# Main_Schematics.net
KiCad netlist of a schematic drawn in Altium Designer
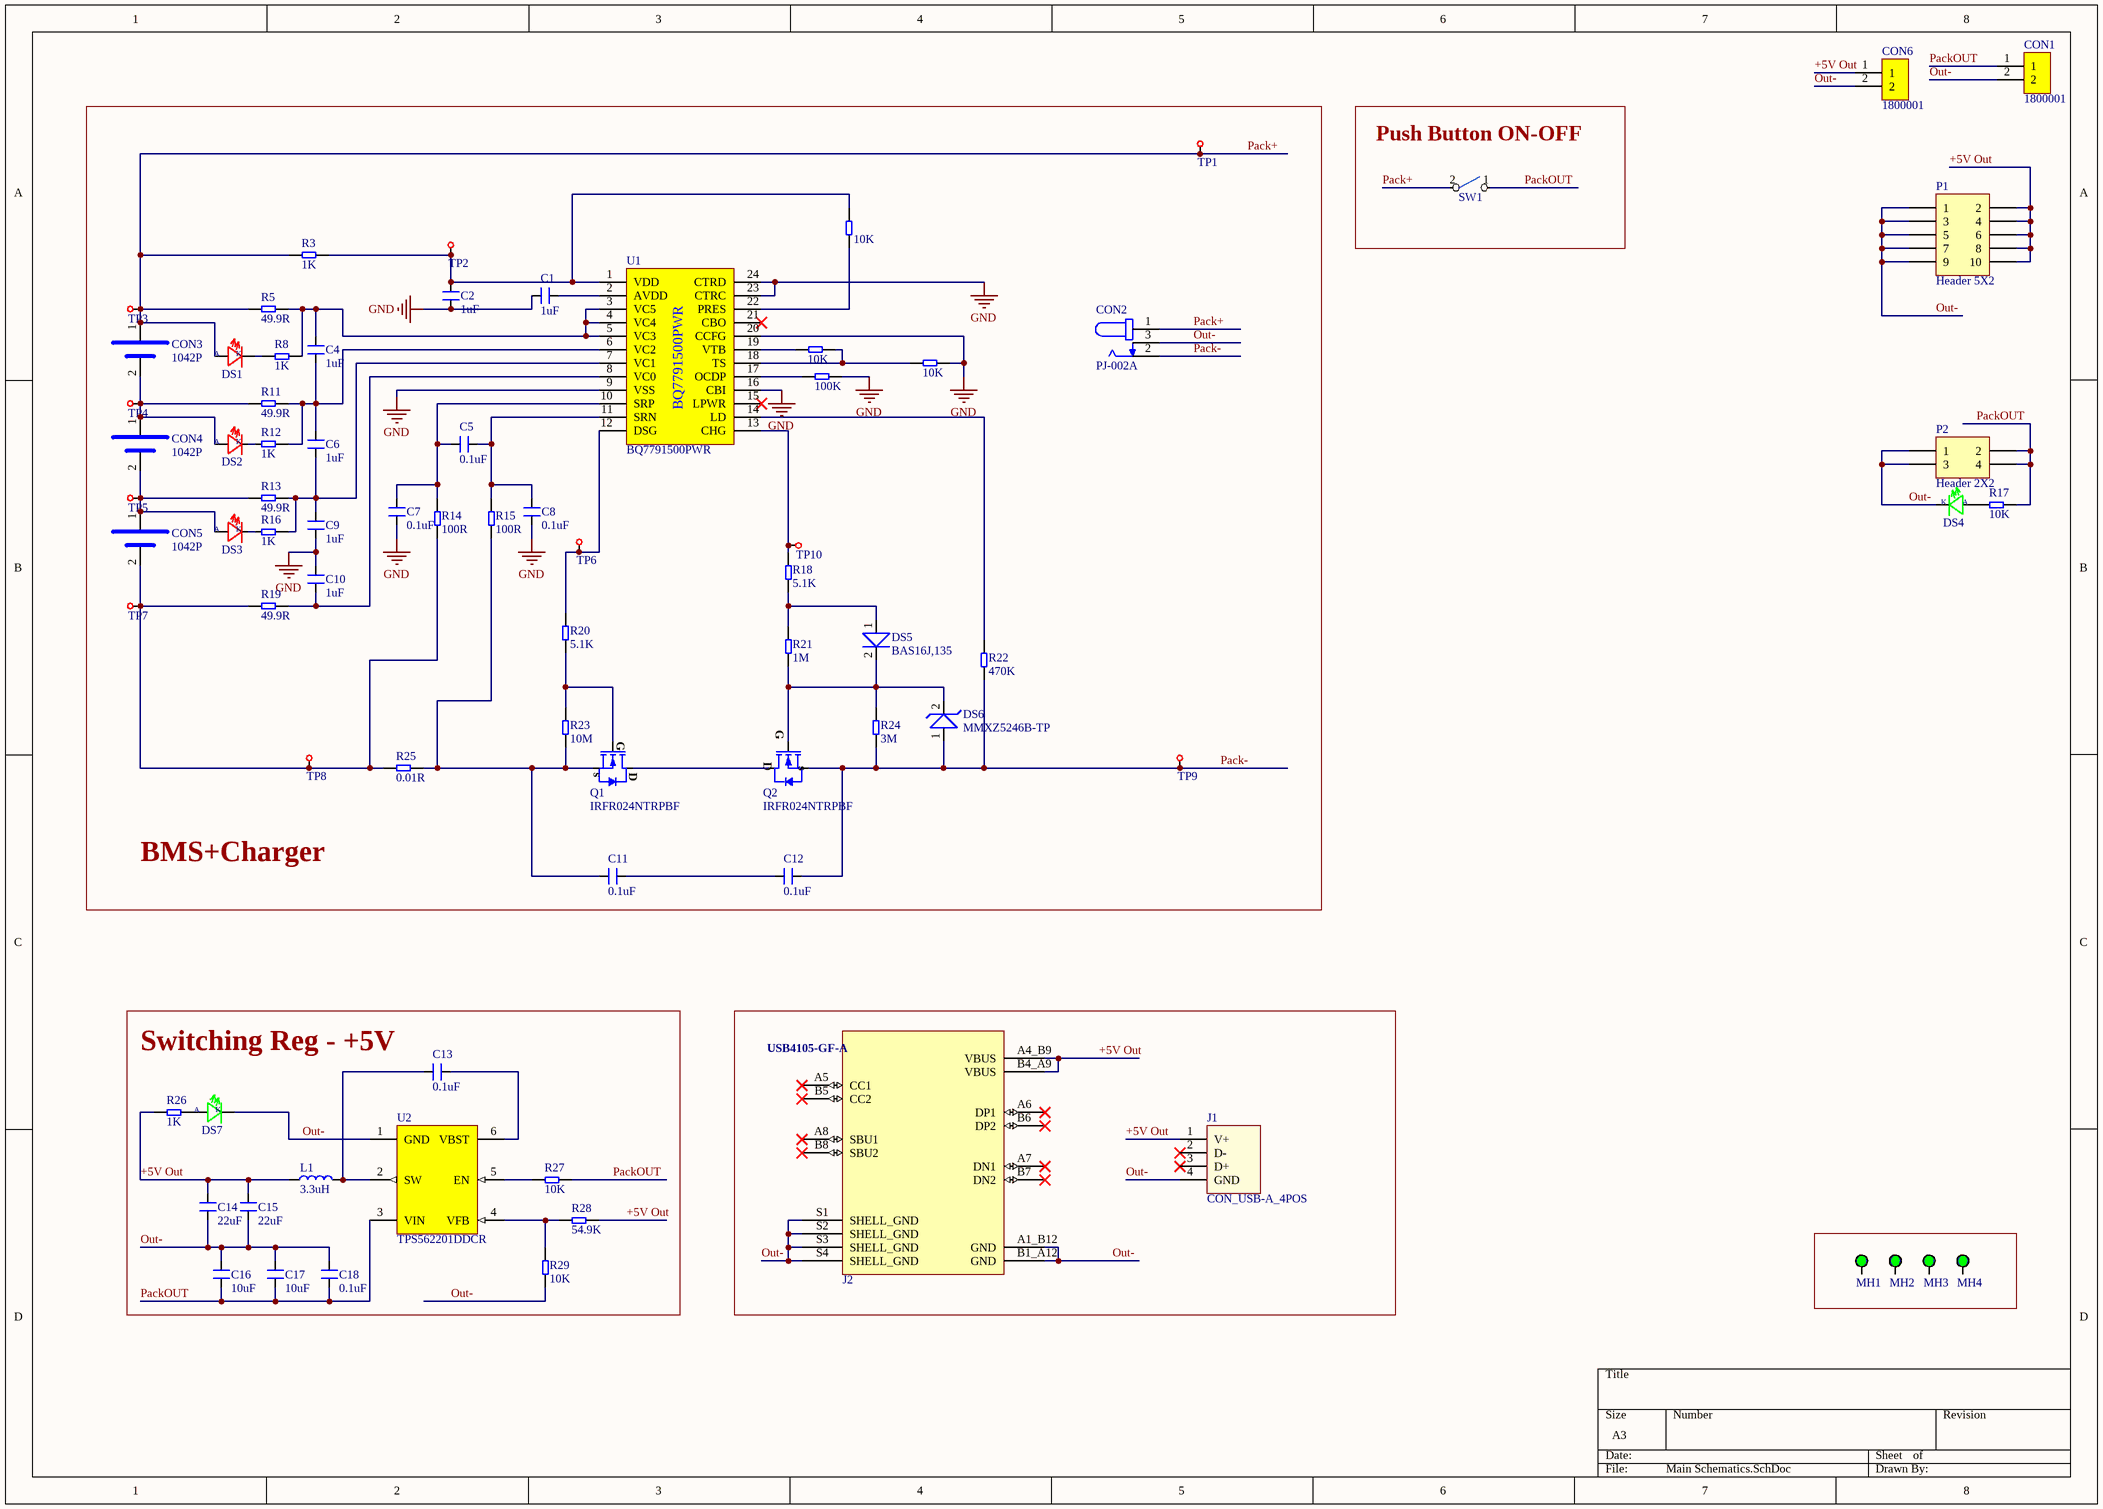
[diagram p0: Main Schematics.SchDoc]

(export (version "E")
  (design (tool "Eeschema 10.0.6"))
  (components
    (comp (ref "C1")
      (value "1uF")
      (footprint "CAP_0805")
      (description "Cap, 1UF, 16V, Mlcc, 0805;")
      (fields
        (field (name "MANUFACTURER") "KEMET")
        (field (name "MANUFACTURER PART NUMBER") "C0805C105Z4VAC7210")
      )
      (libsource (lib "HK_ALTIUM_COM_LIB") (part "CAP_1uF_16V_20%_0805"))
    )
    (comp (ref "C2")
      (value "1uF")
      (footprint "CAP_0805")
      (description "Cap, 1UF, 16V, Mlcc, 0805;")
      (fields
        (field (name "MANUFACTURER") "KEMET")
        (field (name "MANUFACTURER PART NUMBER") "C0805C105Z4VAC7210")
      )
      (libsource (lib "HK_ALTIUM_COM_LIB") (part "CAP_1uF_16V_20%_0805"))
    )
    (comp (ref "C4")
      (value "1uF")
      (footprint "CAP_0805")
      (description "Cap, 1UF, 16V, Mlcc, 0805;")
      (fields
        (field (name "MANUFACTURER") "KEMET")
        (field (name "MANUFACTURER PART NUMBER") "C0805C105Z4VAC7210")
      )
      (libsource (lib "HK_ALTIUM_COM_LIB") (part "CAP_1uF_16V_20%_0805"))
    )
    (comp (ref "C5")
      (value "0.1uF")
      (footprint "CAP_0805")
      (description "Multilayer Ceramic Capacitor, 0.1 uF, 16 V, ± 10%, X7R, 0805 [2012 Metric]")
      (fields
        (field (name "MANUFACTURER") "KEMET")
        (field (name "MANUFACTURER PART NUMBER") "C0805C104K4RACTU")
      )
      (libsource (lib "HK_ALTIUM_COM_LIB") (part "CAP_0.1uF_16V_10%_0805"))
    )
    (comp (ref "C6")
      (value "1uF")
      (footprint "CAP_0805")
      (description "Cap, 1UF, 16V, Mlcc, 0805;")
      (fields
        (field (name "MANUFACTURER") "KEMET")
        (field (name "MANUFACTURER PART NUMBER") "C0805C105Z4VAC7210")
      )
      (libsource (lib "HK_ALTIUM_COM_LIB") (part "CAP_1uF_16V_20%_0805"))
    )
    (comp (ref "C7")
      (value "0.1uF")
      (footprint "CAP_0805")
      (description "Multilayer Ceramic Capacitor, 0.1 uF, 16 V, ± 10%, X7R, 0805 [2012 Metric]")
      (fields
        (field (name "MANUFACTURER") "KEMET")
        (field (name "MANUFACTURER PART NUMBER") "C0805C104K4RACTU")
      )
      (libsource (lib "HK_ALTIUM_COM_LIB") (part "CAP_0.1uF_16V_10%_0805"))
    )
    (comp (ref "C8")
      (value "0.1uF")
      (footprint "CAP_0805")
      (description "Multilayer Ceramic Capacitor, 0.1 uF, 16 V, ± 10%, X7R, 0805 [2012 Metric]")
      (fields
        (field (name "MANUFACTURER") "KEMET")
        (field (name "MANUFACTURER PART NUMBER") "C0805C104K4RACTU")
      )
      (libsource (lib "HK_ALTIUM_COM_LIB") (part "CAP_0.1uF_16V_10%_0805"))
    )
    (comp (ref "C9")
      (value "1uF")
      (footprint "CAP_0805")
      (description "Cap, 1UF, 16V, Mlcc, 0805;")
      (fields
        (field (name "MANUFACTURER") "KEMET")
        (field (name "MANUFACTURER PART NUMBER") "C0805C105Z4VAC7210")
      )
      (libsource (lib "HK_ALTIUM_COM_LIB") (part "CAP_1uF_16V_20%_0805"))
    )
    (comp (ref "C10")
      (value "1uF")
      (footprint "CAP_0805")
      (description "Cap, 1UF, 16V, Mlcc, 0805;")
      (fields
        (field (name "MANUFACTURER") "KEMET")
        (field (name "MANUFACTURER PART NUMBER") "C0805C105Z4VAC7210")
      )
      (libsource (lib "HK_ALTIUM_COM_LIB") (part "CAP_1uF_16V_20%_0805"))
    )
    (comp (ref "C11")
      (value "0.1uF")
      (footprint "CAP_0805")
      (description "Multilayer Ceramic Capacitor, 0.1 uF, 16 V, ± 10%, X7R, 0805 [2012 Metric]")
      (fields
        (field (name "MANUFACTURER") "KEMET")
        (field (name "MANUFACTURER PART NUMBER") "C0805C104K4RACTU")
      )
      (libsource (lib "HK_ALTIUM_COM_LIB") (part "CAP_0.1uF_16V_10%_0805"))
    )
    (comp (ref "C12")
      (value "0.1uF")
      (footprint "CAP_0805")
      (description "Multilayer Ceramic Capacitor, 0.1 uF, 16 V, ± 10%, X7R, 0805 [2012 Metric]")
      (fields
        (field (name "MANUFACTURER") "KEMET")
        (field (name "MANUFACTURER PART NUMBER") "C0805C104K4RACTU")
      )
      (libsource (lib "HK_ALTIUM_COM_LIB") (part "CAP_0.1uF_16V_10%_0805"))
    )
    (comp (ref "C13")
      (value "0.1uF")
      (footprint "CAP_0805")
      (description "SMD Comm X7R 0805 (2012Metric) Ceramic Capacitor 0.079Lx0.049W 2.00mmx1.25mm X7R ±10% 0.1muF")
      (fields
        (field (name "MANUFACTURER") "KEMET")
        (field (name "MANUFACTURER PART NUMBER") "C0805C104K5RAC7210")
      )
      (libsource (lib "HK_ALTIUM_COM_LIB") (part "CAP_0.1uF_50V_10%_0805"))
    )
    (comp (ref "C14")
      (value "22uF")
      (footprint "CAP_0805")
      (description "0805 25 V 22 uF ±20% Tolerance X5R Monolithic Ceramic Chip Capacitor")
      (fields
        (field (name "MANUFACTURER") "Murata Electronics")
        (field (name "MANUFACTURER PART NUMBER") "GRM21BR61E226ME44K")
      )
      (libsource (lib "HK_ALTIUM_COM_LIB") (part "CAP_22uF-25V-20%-0805"))
    )
    (comp (ref "C15")
      (value "22uF")
      (footprint "CAP_0805")
      (description "0805 25 V 22 uF ±20% Tolerance X5R Monolithic Ceramic Chip Capacitor")
      (fields
        (field (name "MANUFACTURER") "Murata Electronics")
        (field (name "MANUFACTURER PART NUMBER") "GRM21BR61E226ME44K")
      )
      (libsource (lib "HK_ALTIUM_COM_LIB") (part "CAP_22uF-25V-20%-0805"))
    )
    (comp (ref "C16")
      (value "10uF")
      (footprint "CAP_1206")
      (description "Multilayer Ceramic Capacitor, 10 uF, 25 V, ± 10%, X5R, 1206 [3216 Metric]")
      (fields (field (name "TOLERANCE") "10%"))
      (libsource (lib "HK_ALTIUM_COM_LIB") (part "CAP_10uF_25V_10%_1206"))
    )
    (comp (ref "C17")
      (value "10uF")
      (footprint "CAP_1206")
      (description "Multilayer Ceramic Capacitor, 10 uF, 25 V, ± 10%, X5R, 1206 [3216 Metric]")
      (fields (field (name "TOLERANCE") "10%"))
      (libsource (lib "HK_ALTIUM_COM_LIB") (part "CAP_10uF_25V_10%_1206"))
    )
    (comp (ref "C18")
      (value "0.1uF")
      (footprint "CAP_0805")
      (description "SMD Comm X7R 0805 (2012Metric) Ceramic Capacitor 0.079Lx0.049W 2.00mmx1.25mm X7R ±10% 0.1muF")
      (fields
        (field (name "MANUFACTURER") "KEMET")
        (field (name "MANUFACTURER PART NUMBER") "C0805C104K5RAC7210")
      )
      (libsource (lib "HK_ALTIUM_COM_LIB") (part "CAP_0.1uF_50V_10%_0805"))
    )
    (comp (ref "CON1")
      (value "1800001")
      (footprint "CON_ED_2POS_TH_2.54mm")
      (description "PCB Terminal Screw 2.54mm 20AWG 160V 6A 2 Position Combicon Control Series")
      (libsource (lib "HK_ALTIUM_COM_LIB") (part "CON_ED_2-pos_2.54mm_Phoenix Contact"))
    )
    (comp (ref "CON2")
      (value "PJ-002A")
      (footprint "CUI_PJ-002A")
      (description "2.0 x 6.5 mm, 2.5 A, Horizontal, Through Hole, Dc Power Jack Connector")
      (libsource (lib "HK_ALTIUM_COM_LIB") (part "CON_ED_DC-JACK_RA_PJ-002A"))
    )
    (comp (ref "CON3")
      (value "1042P")
      (footprint "1042P")
      (description "Cylindrical Battery Contacts, Clips, Holders & Springs SMT Polarized Holder for 18650 Battery")
      (libsource (lib "HK_ALTIUM_COM_LIB") (part "CON_18650_BATT"))
    )
    (comp (ref "CON4")
      (value "1042P")
      (footprint "1042P")
      (description "Cylindrical Battery Contacts, Clips, Holders & Springs SMT Polarized Holder for 18650 Battery")
      (libsource (lib "HK_ALTIUM_COM_LIB") (part "CON_18650_BATT"))
    )
    (comp (ref "CON5")
      (value "1042P")
      (footprint "1042P")
      (description "Cylindrical Battery Contacts, Clips, Holders & Springs SMT Polarized Holder for 18650 Battery")
      (libsource (lib "HK_ALTIUM_COM_LIB") (part "CON_18650_BATT"))
    )
    (comp (ref "CON6")
      (value "1800001")
      (footprint "CON_ED_2POS_TH_2.54mm")
      (description "PCB Terminal Screw 2.54mm 20AWG 160V 6A 2 Position Combicon Control Series")
      (libsource (lib "HK_ALTIUM_COM_LIB") (part "CON_ED_2-pos_2.54mm_Phoenix Contact"))
    )
    (comp (ref "DS1")
      (value "HSMS-C190")
      (footprint "LED_0603")
      (description "LED Low-Power Uni-Color Red 630nm 2.1V 2-Pin Chip LED T/R")
      (fields (field (name "MANUFACTURER") "Broadcom Avago"))
      (libsource (lib "HK_ALTIUM_COM_LIB") (part "LED_Red_0603_2.2V_HSMS-C190"))
    )
    (comp (ref "DS2")
      (value "HSMS-C190")
      (footprint "LED_0603")
      (description "LED Low-Power Uni-Color Red 630nm 2.1V 2-Pin Chip LED T/R")
      (fields (field (name "MANUFACTURER") "Broadcom Avago"))
      (libsource (lib "HK_ALTIUM_COM_LIB") (part "LED_Red_0603_2.2V_HSMS-C190"))
    )
    (comp (ref "DS3")
      (value "HSMS-C190")
      (footprint "LED_0603")
      (description "LED Low-Power Uni-Color Red 630nm 2.1V 2-Pin Chip LED T/R")
      (fields (field (name "MANUFACTURER") "Broadcom Avago"))
      (libsource (lib "HK_ALTIUM_COM_LIB") (part "LED_Red_0603_2.2V_HSMS-C190"))
    )
    (comp (ref "DS4")
      (value "HSMG-C190")
      (footprint "LED_0603")
      (description "Green 572nm LED Indication - Discrete 2.2V 0603 (1608 Metric)")
      (fields (field (name "MANUFACTURER") "Broadcom Avago"))
      (libsource (lib "HK_ALTIUM_COM_LIB") (part "LED_Green_0603_2.2V_HSMG-C190"))
    )
    (comp (ref "DS5")
      (value "BAS16J,135")
      (footprint "SOD323F")
      (description "Rectifier Diode, 1 Phase, 1 Element, 0.25A, 100V V(RRM), Silicon")
      (libsource (lib "HK_ALTIUM_COM_LIB") (part "DIO_100V_0.25A_SOD-323F"))
    )
    (comp (ref "DS6")
      (value "MMXZ5246B-TP")
      (footprint "SOD323 Zener")
      (description "Diode Zener Single 16V 5% 200mW 2-Pin SOD-323 T/R")
      (libsource (lib "HK_ALTIUM_COM_LIB") (part "DIO-Z_16V_200mW_5%_SOD-323"))
    )
    (comp (ref "DS7")
      (value "HSMG-C190")
      (footprint "LED_0603")
      (description "Green 572nm LED Indication - Discrete 2.2V 0603 (1608 Metric)")
      (fields (field (name "MANUFACTURER") "Broadcom Avago"))
      (libsource (lib "HK_ALTIUM_COM_LIB") (part "LED_Green_0603_2.2V_HSMG-C190"))
    )
    (comp (ref "J1")
      (value "CON_USB-A_4POS")
      (footprint "CON_USB_TYPE-A")
      (libsource (lib "HK_ALTIUM_COM_LIB") (part "CON_USB-A_4POS"))
    )
    (comp (ref "J2")
      (value "CON_USB-C (2.0)_USB4105-GF-A")
      (footprint "CON_USB_TYPE-C-2.0 SMD TH")
      (description "Conn USB 2.0 Type C RCP 24 POS 0.3mm/0.5mm Solder RA SMD 24 Terminal 1 Port T/R")
      (libsource (lib "HK_ALTIUM_COM_LIB") (part "CON_USB-C (2.0)_USB4105-GF-A"))
    )
    (comp (ref "L1")
      (value "3.3uH")
      (footprint "Non-Standard_IND 744311330")
      (description "Power Choke Shielded Wirewound 3.3uH/2.75uH 20% 100KHz 6.5A 17.2mOhm DCR T/R")
      (fields (field (name "TOLERANCE") "20%"))
      (libsource (lib "HK_ALTIUM_COM_LIB") (part "IND_3.3uH_6.5A_20%_Non-Std"))
    )
    (comp (ref "MH1")
      (value "MH_3mm")
      (footprint "MH_3mm")
      (description "Mounting Hole 3mm")
      (libsource (lib "HK_ALTIUM_COM_LIB") (part "MH_3mm"))
    )
    (comp (ref "MH2")
      (value "MH_3mm")
      (footprint "MH_3mm")
      (description "Mounting Hole 3mm")
      (libsource (lib "HK_ALTIUM_COM_LIB") (part "MH_3mm"))
    )
    (comp (ref "MH3")
      (value "MH_3mm")
      (footprint "MH_3mm")
      (description "Mounting Hole 3mm")
      (libsource (lib "HK_ALTIUM_COM_LIB") (part "MH_3mm"))
    )
    (comp (ref "MH4")
      (value "MH_3mm")
      (footprint "MH_3mm")
      (description "Mounting Hole 3mm")
      (libsource (lib "HK_ALTIUM_COM_LIB") (part "MH_3mm"))
    )
    (comp (ref "P1")
      (value "Header 5X2")
      (footprint "HDR2X5")
      (description "Header, 5-Pin, Dual row")
      (fields (field (name "PUBLISHER") "Altium Limited"))
      (libsource (lib "Miscellaneous Connectors") (part "Header 5X2"))
    )
    (comp (ref "P2")
      (value "Header 2X2")
      (footprint "HDR2X2")
      (description "Header, 2-Pin, Dual row")
      (fields (field (name "PUBLISHER") "Altium Limited"))
      (libsource (lib "Miscellaneous Connectors") (part "Header 2X2"))
    )
    (comp (ref "Q1")
      (value "IRFR024NTRPBF")
      (footprint "DPAK")
      (description "Mosfet, Power; N-ch; Vdss 55V; Rds(on) 0.075 Ohm; Id 17A; D-pak (TO-252AA); Pd 45W")
      (fields (field (name "MANUFACTURER") "Infineon"))
      (libsource (lib "HK_ALTIUM_COM_LIB") (part "MOSFET-N_55V_17A_DPAK"))
    )
    (comp (ref "Q2")
      (value "IRFR024NTRPBF")
      (footprint "DPAK")
      (description "Mosfet, Power; N-ch; Vdss 55V; Rds(on) 0.075 Ohm; Id 17A; D-pak (TO-252AA); Pd 45W")
      (fields (field (name "MANUFACTURER") "Infineon"))
      (libsource (lib "HK_ALTIUM_COM_LIB") (part "MOSFET-N_55V_17A_DPAK"))
    )
    (comp (ref "R2")
      (value "10K")
      (footprint "RES_0805")
      (description "SMD Chip Resistor, 10 kOhm, ± 1%, 125 mW, 0805 [2012 Metric], Thick Film, General Purpose")
      (fields
        (field (name "MANUFACTURER") "Yageo")
        (field (name "MANUFACTURER PART NUMBER") "RC0805FR-0710KL")
      )
      (libsource (lib "HK_ALTIUM_COM_LIB") (part "RES_10K_1/8W_1%_0805"))
    )
    (comp (ref "R3")
      (value "1K")
      (footprint "RES_0805")
      (description "SMD Chip Resistor, 1 kOhm, ± 1%, 125 mW, 0805 [2012 Metric], Thick Film, General Purpose")
      (fields (field (name "TOLERANCE") "1%"))
      (libsource (lib "HK_ALTIUM_COM_LIB") (part "RES_1K_1/8W_1%_0805"))
    )
    (comp (ref "R5")
      (value "49.9R")
      (footprint "RES_1206")
      (description "SMD Chip Resistor, 49.9 Ohm, ± 1%, 250 mW, 1206 [3216 Metric], Thick Film, General Purpose")
      (libsource (lib "HK_ALTIUM_COM_LIB") (part "RES_49.9R_1/4W_1%_1206"))
    )
    (comp (ref "R7")
      (value "10K")
      (footprint "RES_0805")
      (description "SMD Chip Resistor, 10 kOhm, ± 1%, 125 mW, 0805 [2012 Metric], Thick Film, General Purpose")
      (fields
        (field (name "MANUFACTURER") "Yageo")
        (field (name "MANUFACTURER PART NUMBER") "RC0805FR-0710KL")
      )
      (libsource (lib "HK_ALTIUM_COM_LIB") (part "RES_10K_1/8W_1%_0805"))
    )
    (comp (ref "R8")
      (value "1K")
      (footprint "RES_0805")
      (description "SMD Chip Resistor, 1 kOhm, ± 1%, 125 mW, 0805 [2012 Metric], Thick Film, General Purpose")
      (fields (field (name "TOLERANCE") "1%"))
      (libsource (lib "HK_ALTIUM_COM_LIB") (part "RES_1K_1/8W_1%_0805"))
    )
    (comp (ref "R9")
      (value "10K")
      (footprint "RES_0805")
      (description "SMD Chip Resistor, 10 kOhm, ± 1%, 125 mW, 0805 [2012 Metric], Thick Film, General Purpose")
      (fields
        (field (name "MANUFACTURER") "Yageo")
        (field (name "MANUFACTURER PART NUMBER") "RC0805FR-0710KL")
      )
      (libsource (lib "HK_ALTIUM_COM_LIB") (part "RES_10K_1/8W_1%_0805"))
    )
    (comp (ref "R10")
      (value "100K")
      (footprint "RES_0805")
      (description "SMD Chip Resistor, 100 kOhm, ± 1%, 125 mW, 0805 [2012 Metric], Thick Film, General Purpose")
      (fields
        (field (name "MANUFACTURER") "Yageo")
        (field (name "MANUFACTURER PART NUMBER") "RC0805FR-13100KL")
      )
      (libsource (lib "HK_ALTIUM_COM_LIB") (part "RES_100K_1/8W_1%_0805"))
    )
    (comp (ref "R11")
      (value "49.9R")
      (footprint "RES_1206")
      (description "SMD Chip Resistor, 49.9 Ohm, ± 1%, 250 mW, 1206 [3216 Metric], Thick Film, General Purpose")
      (libsource (lib "HK_ALTIUM_COM_LIB") (part "RES_49.9R_1/4W_1%_1206"))
    )
    (comp (ref "R12")
      (value "1K")
      (footprint "RES_0805")
      (description "SMD Chip Resistor, 1 kOhm, ± 1%, 125 mW, 0805 [2012 Metric], Thick Film, General Purpose")
      (fields (field (name "TOLERANCE") "1%"))
      (libsource (lib "HK_ALTIUM_COM_LIB") (part "RES_1K_1/8W_1%_0805"))
    )
    (comp (ref "R13")
      (value "49.9R")
      (footprint "RES_1206")
      (description "SMD Chip Resistor, 49.9 Ohm, ± 1%, 250 mW, 1206 [3216 Metric], Thick Film, General Purpose")
      (libsource (lib "HK_ALTIUM_COM_LIB") (part "RES_49.9R_1/4W_1%_1206"))
    )
    (comp (ref "R14")
      (value "100R")
      (footprint "RES_0805")
      (description "SMD Chip Resistor, 100 Ohm, ± 1%, 125 mW, 0805 [2012 Metric], Thick Film, General Purpose")
      (fields (field (name "TOLERANCE") "1%"))
      (libsource (lib "HK_ALTIUM_COM_LIB") (part "RES_100R_1/8W_1%_0805"))
    )
    (comp (ref "R15")
      (value "100R")
      (footprint "RES_0805")
      (description "SMD Chip Resistor, 100 Ohm, ± 1%, 125 mW, 0805 [2012 Metric], Thick Film, General Purpose")
      (fields (field (name "TOLERANCE") "1%"))
      (libsource (lib "HK_ALTIUM_COM_LIB") (part "RES_100R_1/8W_1%_0805"))
    )
    (comp (ref "R16")
      (value "1K")
      (footprint "RES_0805")
      (description "SMD Chip Resistor, 1 kOhm, ± 1%, 125 mW, 0805 [2012 Metric], Thick Film, General Purpose")
      (fields (field (name "TOLERANCE") "1%"))
      (libsource (lib "HK_ALTIUM_COM_LIB") (part "RES_1K_1/8W_1%_0805"))
    )
    (comp (ref "R17")
      (value "10K")
      (footprint "RES_0805")
      (description "SMD Chip Resistor, 10 kOhm, ± 1%, 125 mW, 0805 [2012 Metric], Thick Film, General Purpose")
      (fields
        (field (name "MANUFACTURER") "Yageo")
        (field (name "MANUFACTURER PART NUMBER") "RC0805FR-0710KL")
      )
      (libsource (lib "HK_ALTIUM_COM_LIB") (part "RES_10K_1/8W_1%_0805"))
    )
    (comp (ref "R18")
      (value "5.1K")
      (footprint "RES_0805")
      (description "SMD Chip Resistor, 5.1 kOhm, ± 1%, 125 mW, 0805 [2012 Metric], Thick Film, General Purpose")
      (fields (field (name "TOLERANCE") "1%"))
      (libsource (lib "HK_ALTIUM_COM_LIB") (part "RES_5.1K_1/8W_1%_0805"))
    )
    (comp (ref "R19")
      (value "49.9R")
      (footprint "RES_1206")
      (description "SMD Chip Resistor, 49.9 Ohm, ± 1%, 250 mW, 1206 [3216 Metric], Thick Film, General Purpose")
      (libsource (lib "HK_ALTIUM_COM_LIB") (part "RES_49.9R_1/4W_1%_1206"))
    )
    (comp (ref "R20")
      (value "5.1K")
      (footprint "RES_0805")
      (description "SMD Chip Resistor, 5.1 kOhm, ± 1%, 125 mW, 0805 [2012 Metric], Thick Film, General Purpose")
      (fields (field (name "TOLERANCE") "1%"))
      (libsource (lib "HK_ALTIUM_COM_LIB") (part "RES_5.1K_1/8W_1%_0805"))
    )
    (comp (ref "R21")
      (value "1M")
      (footprint "RES_0805")
      (description "SMD Chip Resistor, 1 MOhm, ± 1%, 125 mW, 0805 [2012 Metric], Thick Film, General Purpose")
      (libsource (lib "HK_ALTIUM_COM_LIB") (part "RES_1M_1/8W_1%_0805"))
    )
    (comp (ref "R22")
      (value "470K")
      (footprint "RES_0805")
      (description "SMD Chip Resistor, 470 kOhm, ± 5%, 125 mW, 0805 [2012 Metric], Thick Film, General Purpose")
      (libsource (lib "HK_ALTIUM_COM_LIB") (part "RES_470K_1/8W_5%_0805"))
    )
    (comp (ref "R23")
      (value "10M")
      (footprint "RES_0805")
      (description "Res Thick Film 0805 10M Ohm 5% 0.125W(1/8W) ±100ppm/°C Pad SMD T/R")
      (libsource (lib "HK_ALTIUM_COM_LIB") (part "RES_10M_1/8W_5%_0805"))
    )
    (comp (ref "R24")
      (value "3M")
      (footprint "RES_0805")
      (description "Res Thick Film 0805 3M Ohm 5% 1/8W ±100ppm/°C SMD Paper T/R")
      (libsource (lib "HK_ALTIUM_COM_LIB") (part "RES_3M_1/8W_5%_0805"))
    )
    (comp (ref "R25")
      (value "0.01R")
      (footprint "RES_2010")
      (description "SMD Current Sense Resistor, 10 Milliohm, ± 1%, 500 mW, 2010 [5025 Metric], Metal Film")
      (libsource (lib "HK_ALTIUM_COM_LIB") (part "RES_0.01R_1/2W_1%_2010"))
    )
    (comp (ref "R26")
      (value "1K")
      (footprint "RES_0805")
      (description "SMD Chip Resistor, 1 kOhm, ± 1%, 125 mW, 0805 [2012 Metric], Thick Film, General Purpose")
      (fields (field (name "TOLERANCE") "1%"))
      (libsource (lib "HK_ALTIUM_COM_LIB") (part "RES_1K_1/8W_1%_0805"))
    )
    (comp (ref "R27")
      (value "10K")
      (footprint "RES_0805")
      (description "SMD Chip Resistor, 10 kOhm, ± 1%, 125 mW, 0805 [2012 Metric], Thick Film, General Purpose")
      (fields
        (field (name "MANUFACTURER") "Yageo")
        (field (name "MANUFACTURER PART NUMBER") "RC0805FR-0710KL")
      )
      (libsource (lib "HK_ALTIUM_COM_LIB") (part "RES_10K_1/8W_1%_0805"))
    )
    (comp (ref "R28")
      (value "54.9K")
      (footprint "RES_0805")
      (description "Res Thick Film 0805 54.9K Ohm 1% 1/8W ±100ppm/°C Molded SMD Punched Carrier T/R")
      (libsource (lib "HK_ALTIUM_COM_LIB") (part "RES_54.9K_1/8W_1%_0805"))
    )
    (comp (ref "R29")
      (value "10K")
      (footprint "RES_0805")
      (description "SMD Chip Resistor, 10 kOhm, ± 1%, 125 mW, 0805 [2012 Metric], Thick Film, General Purpose")
      (fields
        (field (name "MANUFACTURER") "Yageo")
        (field (name "MANUFACTURER PART NUMBER") "RC0805FR-0710KL")
      )
      (libsource (lib "HK_ALTIUM_COM_LIB") (part "RES_10K_1/8W_1%_0805"))
    )
    (comp (ref "SW1")
      (value "SW_SPST_Rocker_Mini_6A")
      (footprint "SW_Mini_Rocker")
      (description "SWITCH ROCKER MINI SPST 6A 250V")
      (libsource (lib "HK_ALTIUM_COM_LIB") (part "SW_SPST_Rocker_Mini_6A"))
    )
    (comp (ref "TP1")
      (value "Test Point SMD Round 1.27mm")
      (footprint "Test Point Round 1.27mm")
      (description "Testpoint SMD Round")
      (libsource (lib "HK_ALTIUM_COM_LIB") (part "Test Point SMD Round 1.27mm"))
    )
    (comp (ref "TP2")
      (value "Test Point SMD Round 1.27mm")
      (footprint "Test Point Round 1.27mm")
      (description "Testpoint SMD Round")
      (libsource (lib "HK_ALTIUM_COM_LIB") (part "Test Point SMD Round 1.27mm"))
    )
    (comp (ref "TP3")
      (value "Test Point SMD Round 1.27mm")
      (footprint "Test Point Round 1.27mm")
      (description "Testpoint SMD Round")
      (libsource (lib "HK_ALTIUM_COM_LIB") (part "Test Point SMD Round 1.27mm"))
    )
    (comp (ref "TP4")
      (value "Test Point SMD Round 1.27mm")
      (footprint "Test Point Round 1.27mm")
      (description "Testpoint SMD Round")
      (libsource (lib "HK_ALTIUM_COM_LIB") (part "Test Point SMD Round 1.27mm"))
    )
    (comp (ref "TP5")
      (value "Test Point SMD Round 1.27mm")
      (footprint "Test Point Round 1.27mm")
      (description "Testpoint SMD Round")
      (libsource (lib "HK_ALTIUM_COM_LIB") (part "Test Point SMD Round 1.27mm"))
    )
    (comp (ref "TP6")
      (value "Test Point SMD Round 1.27mm")
      (footprint "Test Point Round 1.27mm")
      (description "Testpoint SMD Round")
      (libsource (lib "HK_ALTIUM_COM_LIB") (part "Test Point SMD Round 1.27mm"))
    )
    (comp (ref "TP7")
      (value "Test Point SMD Round 1.27mm")
      (footprint "Test Point Round 1.27mm")
      (description "Testpoint SMD Round")
      (libsource (lib "HK_ALTIUM_COM_LIB") (part "Test Point SMD Round 1.27mm"))
    )
    (comp (ref "TP8")
      (value "Test Point SMD Round 1.27mm")
      (footprint "Test Point Round 1.27mm")
      (description "Testpoint SMD Round")
      (libsource (lib "HK_ALTIUM_COM_LIB") (part "Test Point SMD Round 1.27mm"))
    )
    (comp (ref "TP9")
      (value "Test Point SMD Round 1.27mm")
      (footprint "Test Point Round 1.27mm")
      (description "Testpoint SMD Round")
      (libsource (lib "HK_ALTIUM_COM_LIB") (part "Test Point SMD Round 1.27mm"))
    )
    (comp (ref "TP10")
      (value "Test Point SMD Round 1.27mm")
      (footprint "Test Point Round 1.27mm")
      (description "Testpoint SMD Round")
      (libsource (lib "HK_ALTIUM_COM_LIB") (part "Test Point SMD Round 1.27mm"))
    )
    (comp (ref "U1")
      (value "BQ7791500PWR")
      (footprint "TSSOP24")
      (description "Battery Protection Li-Ion/Li-Polymer 1mA 0V to 25V 24-Pin TSSOP T/R")
      (libsource (lib "HK_ALTIUM_COM_LIB") (part "IC_BMS_3S_BQ77915_24TSSOP"))
    )
    (comp (ref "U2")
      (value "TPS562201DDCR")
      (footprint "SOT-23-6 Thin")
      (description "IC REG BUCK ADJ 2A SYNC SOT6")
      (libsource (lib "HK_ALTIUM_COM_LIB") (part "REG_ADJ-0.768V-7V_2A_SOT23-6"))
    )
  )
  (nets
    (net (code "1") (name "/+5V Out") (class "Default")
      (node (ref "C14") (pin "2") (pinfunction "2_2") (pintype "passive"))
      (node (ref "C15") (pin "2") (pinfunction "2_2") (pintype "passive"))
      (node (ref "CON6") (pin "1") (pinfunction "1_1") (pintype "passive"))
      (node (ref "J1") (pin "1") (pinfunction "V+_1") (pintype "passive"))
      (node (ref "J2") (pin "A4_B9") (pinfunction "VBUS_A4_B9") (pintype "passive"))
      (node (ref "J2") (pin "B4_A9") (pinfunction "VBUS_B4_A9") (pintype "passive"))
      (node (ref "L1") (pin "1") (pinfunction "1_1") (pintype "passive"))
      (node (ref "P1") (pin "10") (pinfunction "10_10") (pintype "passive"))
      (node (ref "P1") (pin "2") (pinfunction "2_2") (pintype "passive"))
      (node (ref "P1") (pin "4") (pinfunction "4_4") (pintype "passive"))
      (node (ref "P1") (pin "6") (pinfunction "6_6") (pintype "passive"))
      (node (ref "P1") (pin "8") (pinfunction "8_8") (pintype "passive"))
      (node (ref "R26") (pin "1") (pinfunction "1_1") (pintype "passive"))
      (node (ref "R28") (pin "2") (pinfunction "2_2") (pintype "passive"))
    )
    (net (code "2") (name "/Out-") (class "Default")
      (node (ref "C14") (pin "1") (pinfunction "1_1") (pintype "passive"))
      (node (ref "C15") (pin "1") (pinfunction "1_1") (pintype "passive"))
      (node (ref "C16") (pin "2") (pinfunction "2_2") (pintype "passive"))
      (node (ref "C17") (pin "2") (pinfunction "2_2") (pintype "passive"))
      (node (ref "C18") (pin "2") (pinfunction "2_2") (pintype "passive"))
      (node (ref "CON1") (pin "2") (pinfunction "2_2") (pintype "passive"))
      (node (ref "CON2") (pin "3") (pinfunction "3_3") (pintype "passive"))
      (node (ref "CON6") (pin "2") (pinfunction "2_2") (pintype "passive"))
      (node (ref "DS4") (pin "2") (pinfunction "2_2") (pintype "passive"))
      (node (ref "DS7") (pin "2") (pinfunction "2_2") (pintype "passive"))
      (node (ref "J1") (pin "4") (pinfunction "GND_4") (pintype "passive"))
      (node (ref "J2") (pin "A1_B12") (pinfunction "GND_A1_B12") (pintype "passive"))
      (node (ref "J2") (pin "B1_A12") (pinfunction "GND_B1_A12") (pintype "passive"))
      (node (ref "J2") (pin "S1") (pinfunction "SHELL_GND_S1") (pintype "passive"))
      (node (ref "J2") (pin "S2") (pinfunction "SHELL_GND_S2") (pintype "passive"))
      (node (ref "J2") (pin "S3") (pinfunction "SHELL_GND_S3") (pintype "passive"))
      (node (ref "J2") (pin "S4") (pinfunction "SHELL_GND_S4") (pintype "passive"))
      (node (ref "P1") (pin "1") (pinfunction "1_1") (pintype "passive"))
      (node (ref "P1") (pin "3") (pinfunction "3_3") (pintype "passive"))
      (node (ref "P1") (pin "5") (pinfunction "5_5") (pintype "passive"))
      (node (ref "P1") (pin "7") (pinfunction "7_7") (pintype "passive"))
      (node (ref "P1") (pin "9") (pinfunction "9_9") (pintype "passive"))
      (node (ref "P2") (pin "1") (pinfunction "1_1") (pintype "passive"))
      (node (ref "P2") (pin "3") (pinfunction "3_3") (pintype "passive"))
      (node (ref "R29") (pin "1") (pinfunction "1_1") (pintype "passive"))
      (node (ref "U2") (pin "1") (pinfunction "GND_1") (pintype "power_in"))
    )
    (net (code "3") (name "/Pack+") (class "Default")
      (node (ref "CON2") (pin "1") (pinfunction "1_1") (pintype "passive"))
      (node (ref "CON3") (pin "1") (pinfunction "1_1") (pintype "passive"))
      (node (ref "DS1") (pin "1") (pinfunction "1_1") (pintype "passive"))
      (node (ref "R3") (pin "1") (pinfunction "1_1") (pintype "passive"))
      (node (ref "R5") (pin "1") (pinfunction "1_1") (pintype "passive"))
      (node (ref "SW1") (pin "2") (pinfunction "2_2") (pintype "passive"))
      (node (ref "TP1") (pin "1") (pinfunction "1_1") (pintype "passive"))
      (node (ref "TP3") (pin "1") (pinfunction "1_1") (pintype "passive"))
    )
    (net (code "4") (name "/Pack-") (class "Default")
      (node (ref "C12") (pin "1") (pinfunction "1_1") (pintype "passive"))
      (node (ref "CON2") (pin "2") (pinfunction "2_2") (pintype "passive"))
      (node (ref "DS6") (pin "1") (pinfunction "1_1") (pintype "passive"))
      (node (ref "Q2") (pin "3") (pinfunction "S_3") (pintype "passive"))
      (node (ref "R22") (pin "1") (pinfunction "1_1") (pintype "passive"))
      (node (ref "R24") (pin "1") (pinfunction "1_1") (pintype "passive"))
      (node (ref "TP9") (pin "1") (pinfunction "1_1") (pintype "passive"))
    )
    (net (code "5") (name "/PackOUT") (class "Default")
      (node (ref "C16") (pin "1") (pinfunction "1_1") (pintype "passive"))
      (node (ref "C17") (pin "1") (pinfunction "1_1") (pintype "passive"))
      (node (ref "C18") (pin "1") (pinfunction "1_1") (pintype "passive"))
      (node (ref "CON1") (pin "1") (pinfunction "1_1") (pintype "passive"))
      (node (ref "P2") (pin "2") (pinfunction "2_2") (pintype "passive"))
      (node (ref "P2") (pin "4") (pinfunction "4_4") (pintype "passive"))
      (node (ref "R17") (pin "2") (pinfunction "2_2") (pintype "passive"))
      (node (ref "R27") (pin "1") (pinfunction "1_1") (pintype "passive"))
      (node (ref "SW1") (pin "1") (pinfunction "1_1") (pintype "passive"))
      (node (ref "U2") (pin "3") (pinfunction "VIN_3") (pintype "power_in"))
    )
    (net (code "6") (name "GND") (class "Default")
      (node (ref "C1") (pin "1") (pinfunction "1_1") (pintype "passive"))
      (node (ref "C10") (pin "1") (pinfunction "1_1") (pintype "passive"))
      (node (ref "C2") (pin "2") (pinfunction "2_2") (pintype "passive"))
      (node (ref "C7") (pin "1") (pinfunction "1_1") (pintype "passive"))
      (node (ref "C8") (pin "1") (pinfunction "1_1") (pintype "passive"))
      (node (ref "C9") (pin "1") (pinfunction "1_1") (pintype "passive"))
      (node (ref "R10") (pin "2") (pinfunction "2_2") (pintype "passive"))
      (node (ref "R9") (pin "2") (pinfunction "2_2") (pintype "passive"))
      (node (ref "U1") (pin "16") (pinfunction "CBI_16") (pintype "passive"))
      (node (ref "U1") (pin "20") (pinfunction "CCFG_20") (pintype "passive"))
      (node (ref "U1") (pin "23") (pinfunction "CTRC_23") (pintype "passive"))
      (node (ref "U1") (pin "24") (pinfunction "CTRD_24") (pintype "passive"))
      (node (ref "U1") (pin "9") (pinfunction "VSS_9") (pintype "passive"))
    )
    (net (code "7") (name "Net-(C11-Pad1)") (class "Default")
      (node (ref "C11") (pin "1") (pinfunction "1_1") (pintype "passive"))
      (node (ref "C12") (pin "2") (pinfunction "2_2") (pintype "passive"))
    )
    (net (code "8") (name "Net-(CON3-Pad2)") (class "Default")
      (node (ref "CON3") (pin "2") (pinfunction "2_2") (pintype "passive"))
      (node (ref "CON4") (pin "1") (pinfunction "1_1") (pintype "passive"))
      (node (ref "DS2") (pin "1") (pinfunction "1_1") (pintype "passive"))
      (node (ref "R11") (pin "1") (pinfunction "1_1") (pintype "passive"))
      (node (ref "TP4") (pin "1") (pinfunction "1_1") (pintype "passive"))
    )
    (net (code "9") (name "Net-(CON4-Pad2)") (class "Default")
      (node (ref "CON4") (pin "2") (pinfunction "2_2") (pintype "passive"))
      (node (ref "CON5") (pin "1") (pinfunction "1_1") (pintype "passive"))
      (node (ref "DS3") (pin "1") (pinfunction "1_1") (pintype "passive"))
      (node (ref "R13") (pin "1") (pinfunction "1_1") (pintype "passive"))
      (node (ref "TP5") (pin "1") (pinfunction "1_1") (pintype "passive"))
    )
    (net (code "10") (name "Net-(CON5-Pad2)") (class "Default")
      (node (ref "CON5") (pin "2") (pinfunction "2_2") (pintype "passive"))
      (node (ref "R14") (pin "1") (pinfunction "1_1") (pintype "passive"))
      (node (ref "R19") (pin "1") (pinfunction "1_1") (pintype "passive"))
      (node (ref "R25") (pin "1") (pinfunction "1_1") (pintype "passive"))
      (node (ref "TP7") (pin "1") (pinfunction "1_1") (pintype "passive"))
      (node (ref "TP8") (pin "1") (pinfunction "1_1") (pintype "passive"))
    )
    (net (code "11") (name "Net-(DS1-Pad2)") (class "Default")
      (node (ref "DS1") (pin "2") (pinfunction "2_2") (pintype "passive"))
      (node (ref "R8") (pin "1") (pinfunction "1_1") (pintype "passive"))
    )
    (net (code "12") (name "Net-(DS2-Pad2)") (class "Default")
      (node (ref "DS2") (pin "2") (pinfunction "2_2") (pintype "passive"))
      (node (ref "R12") (pin "1") (pinfunction "1_1") (pintype "passive"))
    )
    (net (code "13") (name "Net-(DS3-Pad2)") (class "Default")
      (node (ref "DS3") (pin "2") (pinfunction "2_2") (pintype "passive"))
      (node (ref "R16") (pin "1") (pinfunction "1_1") (pintype "passive"))
    )
    (net (code "14") (name "Net-(DS4-Pad1)") (class "Default")
      (node (ref "DS4") (pin "1") (pinfunction "1_1") (pintype "passive"))
      (node (ref "R17") (pin "1") (pinfunction "1_1") (pintype "passive"))
    )
    (net (code "15") (name "Net-(DS5-Pad1)") (class "Default")
      (node (ref "DS5") (pin "1") (pinfunction "1_1") (pintype "passive"))
      (node (ref "R18") (pin "1") (pinfunction "1_1") (pintype "passive"))
      (node (ref "R21") (pin "2") (pinfunction "2_2") (pintype "passive"))
    )
    (net (code "16") (name "Net-(DS7-Pad1)") (class "Default")
      (node (ref "DS7") (pin "1") (pinfunction "1_1") (pintype "passive"))
      (node (ref "R26") (pin "2") (pinfunction "2_2") (pintype "passive"))
    )
    (net (code "17") (name "Net-(Q1-D)") (class "Default")
      (node (ref "Q1") (pin "2") (pinfunction "D_2") (pintype "passive"))
      (node (ref "Q2") (pin "2") (pinfunction "D_2") (pintype "passive"))
    )
    (net (code "18") (name "Net-(Q1-G)") (class "Default")
      (node (ref "Q1") (pin "1") (pinfunction "G_1") (pintype "passive"))
      (node (ref "R20") (pin "1") (pinfunction "1_1") (pintype "passive"))
      (node (ref "R23") (pin "2") (pinfunction "2_2") (pintype "passive"))
    )
    (net (code "19") (name "Net-(Q1-S)") (class "Default")
      (node (ref "C11") (pin "2") (pinfunction "2_2") (pintype "passive"))
      (node (ref "Q1") (pin "3") (pinfunction "S_3") (pintype "passive"))
      (node (ref "R15") (pin "1") (pinfunction "1_1") (pintype "passive"))
      (node (ref "R23") (pin "1") (pinfunction "1_1") (pintype "passive"))
      (node (ref "R25") (pin "2") (pinfunction "2_2") (pintype "passive"))
    )
    (net (code "20") (name "Net-(Q2-G)") (class "Default")
      (node (ref "DS5") (pin "2") (pinfunction "2_2") (pintype "passive"))
      (node (ref "DS6") (pin "2") (pinfunction "2_2") (pintype "passive"))
      (node (ref "Q2") (pin "1") (pinfunction "G_1") (pintype "passive"))
      (node (ref "R21") (pin "1") (pinfunction "1_1") (pintype "passive"))
      (node (ref "R24") (pin "2") (pinfunction "2_2") (pintype "passive"))
    )
    (net (code "21") (name "Net-(U1-AVDD)") (class "Default")
      (node (ref "C1") (pin "2") (pinfunction "2_2") (pintype "passive"))
      (node (ref "U1") (pin "2") (pinfunction "AVDD_2") (pintype "passive"))
    )
    (net (code "22") (name "Net-(U1-CHG)") (class "Default")
      (node (ref "R18") (pin "2") (pinfunction "2_2") (pintype "passive"))
      (node (ref "TP10") (pin "1") (pinfunction "1_1") (pintype "passive"))
      (node (ref "U1") (pin "13") (pinfunction "CHG_13") (pintype "passive"))
    )
    (net (code "23") (name "Net-(U1-DSG)") (class "Default")
      (node (ref "R20") (pin "2") (pinfunction "2_2") (pintype "passive"))
      (node (ref "TP6") (pin "1") (pinfunction "1_1") (pintype "passive"))
      (node (ref "U1") (pin "12") (pinfunction "DSG_12") (pintype "passive"))
    )
    (net (code "24") (name "Net-(U1-LD)") (class "Default")
      (node (ref "R22") (pin "2") (pinfunction "2_2") (pintype "passive"))
      (node (ref "U1") (pin "14") (pinfunction "LD_14") (pintype "passive"))
    )
    (net (code "25") (name "Net-(U1-OCDP)") (class "Default")
      (node (ref "R10") (pin "1") (pinfunction "1_1") (pintype "passive"))
      (node (ref "U1") (pin "17") (pinfunction "OCDP_17") (pintype "passive"))
    )
    (net (code "26") (name "Net-(U1-PRES)") (class "Default")
      (node (ref "R2") (pin "1") (pinfunction "1_1") (pintype "passive"))
      (node (ref "U1") (pin "22") (pinfunction "PRES_22") (pintype "passive"))
    )
    (net (code "27") (name "Net-(U1-SRN)") (class "Default")
      (node (ref "C5") (pin "1") (pinfunction "1_1") (pintype "passive"))
      (node (ref "C8") (pin "2") (pinfunction "2_2") (pintype "passive"))
      (node (ref "R15") (pin "2") (pinfunction "2_2") (pintype "passive"))
      (node (ref "U1") (pin "11") (pinfunction "SRN_11") (pintype "passive"))
    )
    (net (code "28") (name "Net-(U1-SRP)") (class "Default")
      (node (ref "C5") (pin "2") (pinfunction "2_2") (pintype "passive"))
      (node (ref "C7") (pin "2") (pinfunction "2_2") (pintype "passive"))
      (node (ref "R14") (pin "2") (pinfunction "2_2") (pintype "passive"))
      (node (ref "U1") (pin "10") (pinfunction "SRP_10") (pintype "passive"))
    )
    (net (code "29") (name "Net-(U1-TS)") (class "Default")
      (node (ref "R7") (pin "2") (pinfunction "2_2") (pintype "passive"))
      (node (ref "R9") (pin "1") (pinfunction "1_1") (pintype "passive"))
      (node (ref "U1") (pin "18") (pinfunction "TS_18") (pintype "passive"))
    )
    (net (code "30") (name "Net-(U1-VC0)") (class "Default")
      (node (ref "C10") (pin "2") (pinfunction "2_2") (pintype "passive"))
      (node (ref "R19") (pin "2") (pinfunction "2_2") (pintype "passive"))
      (node (ref "U1") (pin "8") (pinfunction "VC0_8") (pintype "passive"))
    )
    (net (code "31") (name "Net-(U1-VC1)") (class "Default")
      (node (ref "C6") (pin "1") (pinfunction "1_1") (pintype "passive"))
      (node (ref "C9") (pin "2") (pinfunction "2_2") (pintype "passive"))
      (node (ref "R13") (pin "2") (pinfunction "2_2") (pintype "passive"))
      (node (ref "R16") (pin "2") (pinfunction "2_2") (pintype "passive"))
      (node (ref "U1") (pin "7") (pinfunction "VC1_7") (pintype "passive"))
    )
    (net (code "32") (name "Net-(U1-VC2)") (class "Default")
      (node (ref "C4") (pin "1") (pinfunction "1_1") (pintype "passive"))
      (node (ref "C6") (pin "2") (pinfunction "2_2") (pintype "passive"))
      (node (ref "R11") (pin "2") (pinfunction "2_2") (pintype "passive"))
      (node (ref "R12") (pin "2") (pinfunction "2_2") (pintype "passive"))
      (node (ref "U1") (pin "6") (pinfunction "VC2_6") (pintype "passive"))
    )
    (net (code "33") (name "Net-(U1-VC3)") (class "Default")
      (node (ref "C4") (pin "2") (pinfunction "2_2") (pintype "passive"))
      (node (ref "R5") (pin "2") (pinfunction "2_2") (pintype "passive"))
      (node (ref "R8") (pin "2") (pinfunction "2_2") (pintype "passive"))
      (node (ref "U1") (pin "3") (pinfunction "VC5_3") (pintype "passive"))
      (node (ref "U1") (pin "4") (pinfunction "VC4_4") (pintype "passive"))
      (node (ref "U1") (pin "5") (pinfunction "VC3_5") (pintype "passive"))
    )
    (net (code "34") (name "Net-(U1-VDD)") (class "Default")
      (node (ref "C2") (pin "1") (pinfunction "1_1") (pintype "passive"))
      (node (ref "R2") (pin "2") (pinfunction "2_2") (pintype "passive"))
      (node (ref "R3") (pin "2") (pinfunction "2_2") (pintype "passive"))
      (node (ref "TP2") (pin "1") (pinfunction "1_1") (pintype "passive"))
      (node (ref "U1") (pin "1") (pinfunction "VDD_1") (pintype "passive"))
    )
    (net (code "35") (name "Net-(U1-VTB)") (class "Default")
      (node (ref "R7") (pin "1") (pinfunction "1_1") (pintype "passive"))
      (node (ref "U1") (pin "19") (pinfunction "VTB_19") (pintype "passive"))
    )
    (net (code "36") (name "Net-(U2-EN)") (class "Default")
      (node (ref "R27") (pin "2") (pinfunction "2_2") (pintype "passive"))
      (node (ref "U2") (pin "5") (pinfunction "EN_5") (pintype "input"))
    )
    (net (code "37") (name "Net-(U2-SW)") (class "Default")
      (node (ref "C13") (pin "1") (pinfunction "1_1") (pintype "passive"))
      (node (ref "L1") (pin "2") (pinfunction "1_2") (pintype "passive"))
      (node (ref "U2") (pin "2") (pinfunction "SW_2") (pintype "output"))
    )
    (net (code "38") (name "Net-(U2-VBST)") (class "Default")
      (node (ref "C13") (pin "2") (pinfunction "2_2") (pintype "passive"))
      (node (ref "U2") (pin "6") (pinfunction "VBST_6") (pintype "passive"))
    )
    (net (code "39") (name "Net-(U2-VFB)") (class "Default")
      (node (ref "R28") (pin "1") (pinfunction "1_1") (pintype "passive"))
      (node (ref "R29") (pin "2") (pinfunction "2_2") (pintype "passive"))
      (node (ref "U2") (pin "4") (pinfunction "VFB_4") (pintype "input"))
    )
    (net (code "40") (name "unconnected-(J1-D+-Pad3)") (class "Default")
      (node (ref "J1") (pin "3") (pinfunction "D+_3") (pintype "passive+no_connect"))
    )
    (net (code "41") (name "unconnected-(J1-D--Pad2)") (class "Default")
      (node (ref "J1") (pin "2") (pinfunction "D-_2") (pintype "passive+no_connect"))
    )
    (net (code "42") (name "unconnected-(J2-CC1-PadA5)") (class "Default")
      (node (ref "J2") (pin "A5") (pinfunction "CC1_A5") (pintype "bidirectional+no_connect"))
    )
    (net (code "43") (name "unconnected-(J2-CC2-PadB5)") (class "Default")
      (node (ref "J2") (pin "B5") (pinfunction "CC2_B5") (pintype "bidirectional+no_connect"))
    )
    (net (code "44") (name "unconnected-(J2-DN1-PadA7)") (class "Default")
      (node (ref "J2") (pin "A7") (pinfunction "DN1_A7") (pintype "bidirectional+no_connect"))
    )
    (net (code "45") (name "unconnected-(J2-DN2-PadB7)") (class "Default")
      (node (ref "J2") (pin "B7") (pinfunction "DN2_B7") (pintype "bidirectional+no_connect"))
    )
    (net (code "46") (name "unconnected-(J2-DP1-PadA6)") (class "Default")
      (node (ref "J2") (pin "A6") (pinfunction "DP1_A6") (pintype "bidirectional+no_connect"))
    )
    (net (code "47") (name "unconnected-(J2-DP2-PadB6)") (class "Default")
      (node (ref "J2") (pin "B6") (pinfunction "DP2_B6") (pintype "bidirectional+no_connect"))
    )
    (net (code "48") (name "unconnected-(J2-SBU1-PadA8)") (class "Default")
      (node (ref "J2") (pin "A8") (pinfunction "SBU1_A8") (pintype "bidirectional+no_connect"))
    )
    (net (code "49") (name "unconnected-(J2-SBU2-PadB8)") (class "Default")
      (node (ref "J2") (pin "B8") (pinfunction "SBU2_B8") (pintype "bidirectional+no_connect"))
    )
    (net (code "50") (name "unconnected-(MH1-Pad1)") (class "Default")
      (node (ref "MH1") (pin "1") (pinfunction "1_1") (pintype "passive"))
    )
    (net (code "51") (name "unconnected-(MH2-Pad1)") (class "Default")
      (node (ref "MH2") (pin "1") (pinfunction "1_1") (pintype "passive"))
    )
    (net (code "52") (name "unconnected-(MH3-Pad1)") (class "Default")
      (node (ref "MH3") (pin "1") (pinfunction "1_1") (pintype "passive"))
    )
    (net (code "53") (name "unconnected-(MH4-Pad1)") (class "Default")
      (node (ref "MH4") (pin "1") (pinfunction "1_1") (pintype "passive"))
    )
    (net (code "54") (name "unconnected-(U1-CBO-Pad21)") (class "Default")
      (node (ref "U1") (pin "21") (pinfunction "CBO_21") (pintype "passive+no_connect"))
    )
    (net (code "55") (name "unconnected-(U1-LPWR-Pad15)") (class "Default")
      (node (ref "U1") (pin "15") (pinfunction "LPWR_15") (pintype "passive+no_connect"))
    )
  )
)
